# DisplayConn.net
KiCad netlist of a schematic drawn in Altium Designer
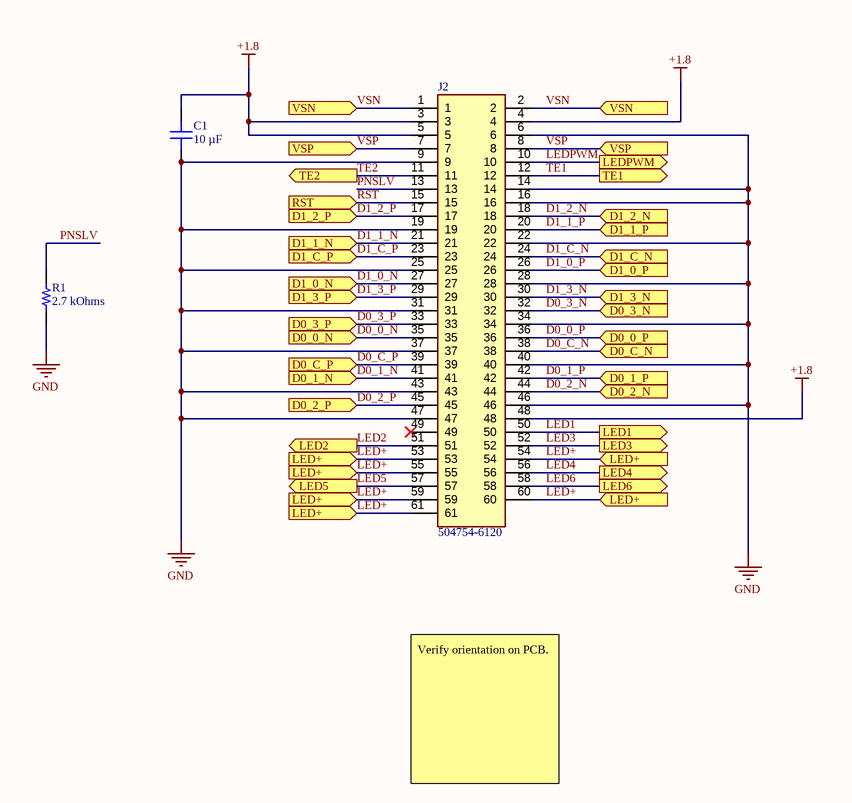
[diagram p0: DisplayConn.SchDoc]

(export (version "E")
  (design (tool "Eeschema 10.0.6"))
  (components
    (comp (ref "C1")
      (value "10 µF")
      (footprint "CAP 0603_1608")
      (description "CAP CER 10UF 16V X5R 0603")
      (fields
        (field (name "PART NUMBER") "GRM188R61C106MA73D")
        (field (name "MANUFACTURER") "Murata Electronics")
      )
      (libsource (lib "Celestial Altium Library - altium_library") (part "Capacitor"))
    )
    (comp (ref "J2")
      (value "504754-6120")
      (footprint "SamacSys:5047546120")
      (description "Connector")
      (fields (field (name "MOUSER PART NUMBER") "538-504754-6120"))
      (libsource (lib "*") (part "504754-6120"))
    )
    (comp (ref "R1")
      (value "2.7 kOhms")
      (footprint "RES 0201_0603")
      (description "RES 2.7K OHM 5% 1/20W 0201 SMD")
      (fields
        (field (name "PART NUMBER") "ERJ-U01J272C")
        (field (name "MANUFACTURER") "Panasonic Electronic Components")
      )
      (libsource (lib "Celestial Altium Library - altium_library") (part "Resistor"))
    )
  )
  (nets
    (net (code "1") (name "+1.8") (class "Default")
      (node (ref "C1") (pin "2") (pinfunction "2_2") (pintype "passive"))
      (node (ref "J2") (pin "3") (pinfunction "3_3") (pintype "passive"))
      (node (ref "J2") (pin "4") (pinfunction "4_4") (pintype "passive"))
      (node (ref "J2") (pin "48") (pinfunction "48_48") (pintype "passive"))
      (node (ref "J2") (pin "5") (pinfunction "5_5") (pintype "passive"))
    )
    (net (code "2") (name "/D0_0_N") (class "Default")
      (node (ref "J2") (pin "35") (pinfunction "35_35") (pintype "passive"))
    )
    (net (code "3") (name "/D0_0_P") (class "Default")
      (node (ref "J2") (pin "36") (pinfunction "36_36") (pintype "passive"))
    )
    (net (code "4") (name "/D0_1_N") (class "Default")
      (node (ref "J2") (pin "41") (pinfunction "41_41") (pintype "passive"))
    )
    (net (code "5") (name "/D0_1_P") (class "Default")
      (node (ref "J2") (pin "42") (pinfunction "42_42") (pintype "passive"))
    )
    (net (code "6") (name "/D0_2_N") (class "Default")
      (node (ref "J2") (pin "44") (pinfunction "44_44") (pintype "passive"))
    )
    (net (code "7") (name "/D0_2_P") (class "Default")
      (node (ref "J2") (pin "45") (pinfunction "45_45") (pintype "passive"))
    )
    (net (code "8") (name "/D0_3_N") (class "Default")
      (node (ref "J2") (pin "32") (pinfunction "32_32") (pintype "passive"))
    )
    (net (code "9") (name "/D0_3_P") (class "Default")
      (node (ref "J2") (pin "33") (pinfunction "33_33") (pintype "passive"))
    )
    (net (code "10") (name "/D0_C_N") (class "Default")
      (node (ref "J2") (pin "38") (pinfunction "38_38") (pintype "passive"))
    )
    (net (code "11") (name "/D0_C_P") (class "Default")
      (node (ref "J2") (pin "39") (pinfunction "39_39") (pintype "passive"))
    )
    (net (code "12") (name "/D1_0_N") (class "Default")
      (node (ref "J2") (pin "27") (pinfunction "27_27") (pintype "passive"))
    )
    (net (code "13") (name "/D1_0_P") (class "Default")
      (node (ref "J2") (pin "26") (pinfunction "26_26") (pintype "passive"))
    )
    (net (code "14") (name "/D1_1_N") (class "Default")
      (node (ref "J2") (pin "21") (pinfunction "21_21") (pintype "passive"))
    )
    (net (code "15") (name "/D1_1_P") (class "Default")
      (node (ref "J2") (pin "20") (pinfunction "20_20") (pintype "passive"))
    )
    (net (code "16") (name "/D1_2_N") (class "Default")
      (node (ref "J2") (pin "18") (pinfunction "18_18") (pintype "passive"))
    )
    (net (code "17") (name "/D1_2_P") (class "Default")
      (node (ref "J2") (pin "17") (pinfunction "17_17") (pintype "passive"))
    )
    (net (code "18") (name "/D1_3_N") (class "Default")
      (node (ref "J2") (pin "30") (pinfunction "30_30") (pintype "passive"))
    )
    (net (code "19") (name "/D1_3_P") (class "Default")
      (node (ref "J2") (pin "29") (pinfunction "29_29") (pintype "passive"))
    )
    (net (code "20") (name "/D1_C_N") (class "Default")
      (node (ref "J2") (pin "24") (pinfunction "24_24") (pintype "passive"))
    )
    (net (code "21") (name "/D1_C_P") (class "Default")
      (node (ref "J2") (pin "23") (pinfunction "23_23") (pintype "passive"))
    )
    (net (code "22") (name "/LED+") (class "Default")
      (node (ref "J2") (pin "53") (pinfunction "53_53") (pintype "passive"))
      (node (ref "J2") (pin "54") (pinfunction "54_54") (pintype "passive"))
      (node (ref "J2") (pin "55") (pinfunction "55_55") (pintype "passive"))
      (node (ref "J2") (pin "59") (pinfunction "59_59") (pintype "passive"))
      (node (ref "J2") (pin "60") (pinfunction "60_60") (pintype "passive"))
      (node (ref "J2") (pin "61") (pinfunction "61_61") (pintype "passive"))
    )
    (net (code "23") (name "/LED1") (class "Default")
      (node (ref "J2") (pin "50") (pinfunction "50_50") (pintype "passive"))
    )
    (net (code "24") (name "/LED2") (class "Default")
      (node (ref "J2") (pin "51") (pinfunction "51_51") (pintype "passive"))
    )
    (net (code "25") (name "/LED3") (class "Default")
      (node (ref "J2") (pin "52") (pinfunction "52_52") (pintype "passive"))
    )
    (net (code "26") (name "/LED4") (class "Default")
      (node (ref "J2") (pin "56") (pinfunction "56_56") (pintype "passive"))
    )
    (net (code "27") (name "/LED5") (class "Default")
      (node (ref "J2") (pin "57") (pinfunction "57_57") (pintype "passive"))
    )
    (net (code "28") (name "/LED6") (class "Default")
      (node (ref "J2") (pin "58") (pinfunction "58_58") (pintype "passive"))
    )
    (net (code "29") (name "/LEDPWM") (class "Default")
      (node (ref "J2") (pin "10") (pinfunction "10_10") (pintype "passive"))
    )
    (net (code "30") (name "/PNSLV") (class "Default")
      (node (ref "J2") (pin "13") (pinfunction "13_13") (pintype "passive"))
      (node (ref "R1") (pin "2") (pinfunction "2_2") (pintype "passive"))
    )
    (net (code "31") (name "/RST") (class "Default")
      (node (ref "J2") (pin "15") (pinfunction "15_15") (pintype "passive"))
    )
    (net (code "32") (name "/TE1") (class "Default")
      (node (ref "J2") (pin "12") (pinfunction "12_12") (pintype "passive"))
    )
    (net (code "33") (name "/TE2") (class "Default")
      (node (ref "J2") (pin "11") (pinfunction "11_11") (pintype "passive"))
    )
    (net (code "34") (name "/VSN") (class "Default")
      (node (ref "J2") (pin "1") (pinfunction "1_1") (pintype "passive"))
      (node (ref "J2") (pin "2") (pinfunction "2_2") (pintype "passive"))
    )
    (net (code "35") (name "/VSP") (class "Default")
      (node (ref "J2") (pin "7") (pinfunction "7_7") (pintype "passive"))
      (node (ref "J2") (pin "8") (pinfunction "8_8") (pintype "passive"))
    )
    (net (code "36") (name "GND") (class "Default")
      (node (ref "C1") (pin "1") (pinfunction "1_1") (pintype "passive"))
      (node (ref "J2") (pin "14") (pinfunction "14_14") (pintype "passive"))
      (node (ref "J2") (pin "16") (pinfunction "16_16") (pintype "passive"))
      (node (ref "J2") (pin "19") (pinfunction "19_19") (pintype "passive"))
      (node (ref "J2") (pin "22") (pinfunction "22_22") (pintype "passive"))
      (node (ref "J2") (pin "25") (pinfunction "25_25") (pintype "passive"))
      (node (ref "J2") (pin "28") (pinfunction "28_28") (pintype "passive"))
      (node (ref "J2") (pin "31") (pinfunction "31_31") (pintype "passive"))
      (node (ref "J2") (pin "34") (pinfunction "34_34") (pintype "passive"))
      (node (ref "J2") (pin "37") (pinfunction "37_37") (pintype "passive"))
      (node (ref "J2") (pin "40") (pinfunction "40_40") (pintype "passive"))
      (node (ref "J2") (pin "43") (pinfunction "43_43") (pintype "passive"))
      (node (ref "J2") (pin "46") (pinfunction "46_46") (pintype "passive"))
      (node (ref "J2") (pin "47") (pinfunction "47_47") (pintype "passive"))
      (node (ref "J2") (pin "6") (pinfunction "6_6") (pintype "passive"))
      (node (ref "J2") (pin "9") (pinfunction "9_9") (pintype "passive"))
      (node (ref "R1") (pin "1") (pinfunction "1_1") (pintype "passive"))
    )
    (net (code "37") (name "unconnected-(J2-Pad49)") (class "Default")
      (node (ref "J2") (pin "49") (pinfunction "49_49") (pintype "passive+no_connect"))
    )
  )
)
